# RS232.net
KiCad netlist of a schematic drawn in Altium Designer
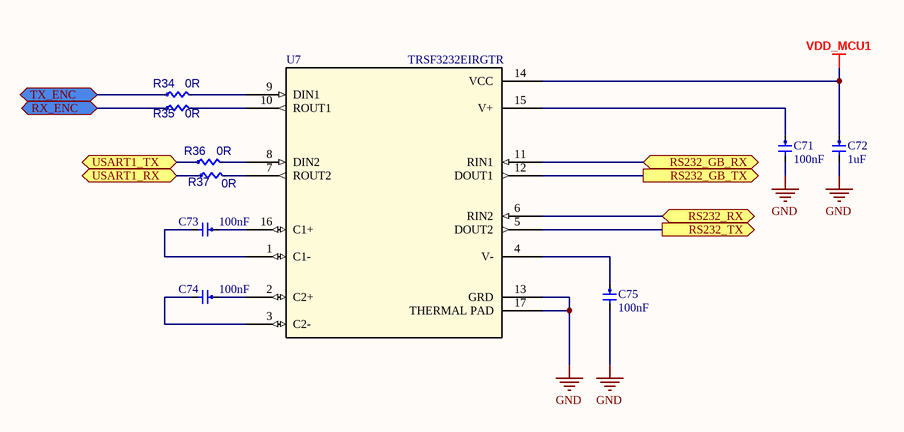
[diagram p0: RS232.SchDoc]

(export (version "E")
  (design (tool "Eeschema 10.0.6"))
  (components
    (comp (ref "C71")
      (value "GRM155R71H104KE14D")
      (footprint "CAP0402")
      (description "CAP CER 0.1UF 50V X7R 0402")
      (fields
        (field (name "TOLERANCE") "10%")
        (field (name "CAPACITANCE") "100nF")
        (field (name "VOLTAGE") "50V")
      )
      (libsource (lib "CH961_CARRIER") (part "CMP-01036-1"))
    )
    (comp (ref "C72")
      (value "CC0402KRX5R8BB105")
      (footprint "CAP0402")
      (description "CAP CER 1UF 25V X5R 0402")
      (fields
        (field (name "VOLTAGE") "25V")
        (field (name "TOLERANCE") "10%")
        (field (name "CAPACITANCE") "1uF")
      )
      (libsource (lib "CH961_CARRIER") (part "CMP-00520-1"))
    )
    (comp (ref "C73")
      (value "GRM155R71H104KE14D")
      (footprint "CAP0402")
      (description "CAP CER 0.1UF 50V X7R 0402")
      (fields
        (field (name "TOLERANCE") "10%")
        (field (name "CAPACITANCE") "100nF")
        (field (name "VOLTAGE") "50V")
      )
      (libsource (lib "CH961_CARRIER") (part "CMP-01036-1"))
    )
    (comp (ref "C74")
      (value "GRM155R71H104KE14D")
      (footprint "CAP0402")
      (description "CAP CER 0.1UF 50V X7R 0402")
      (fields
        (field (name "TOLERANCE") "10%")
        (field (name "CAPACITANCE") "100nF")
        (field (name "VOLTAGE") "50V")
      )
      (libsource (lib "CH961_CARRIER") (part "CMP-01036-1"))
    )
    (comp (ref "C75")
      (value "GRM155R71H104KE14D")
      (footprint "CAP0402")
      (description "CAP CER 0.1UF 50V X7R 0402")
      (fields
        (field (name "TOLERANCE") "10%")
        (field (name "CAPACITANCE") "100nF")
        (field (name "VOLTAGE") "50V")
      )
      (libsource (lib "CH961_CARRIER") (part "CMP-01036-1"))
    )
    (comp (ref "R34")
      (value "ERJ-2RKF4701X")
      (footprint "RES0402")
      (description "RES SMD 4.7K OHM 1% 1/10W 0402")
      (fields (field (name "TOLERANCE") "1%") (field (name "RESISTANCE") "0R"))
      (libsource (lib "rtr") (part "CMP-00607-1"))
    )
    (comp (ref "R35")
      (value "ERJ-2RKF4701X")
      (footprint "RES0402")
      (description "RES SMD 4.7K OHM 1% 1/10W 0402")
      (fields (field (name "TOLERANCE") "1%") (field (name "RESISTANCE") "0R"))
      (libsource (lib "rtr") (part "CMP-00607-1"))
    )
    (comp (ref "R36")
      (value "ERJ-2RKF4701X")
      (footprint "RES0402")
      (description "RES SMD 4.7K OHM 1% 1/10W 0402")
      (fields (field (name "TOLERANCE") "1%") (field (name "RESISTANCE") "0R"))
      (libsource (lib "rtr") (part "CMP-00607-1"))
    )
    (comp (ref "R37")
      (value "ERJ-2RKF4701X")
      (footprint "RES0402")
      (description "RES SMD 4.7K OHM 1% 1/10W 0402")
      (fields (field (name "TOLERANCE") "1%") (field (name "RESISTANCE") "0R"))
      (libsource (lib "rtr") (part "CMP-00607-1"))
    )
    (comp (ref "U7")
      (value "TRSF3232EIRGTR")
      (footprint "TRSF3232EIRGTR")
      (description "No Description Available")
      (libsource (lib "TRSF3232EIRGTR") (part "TRSF3232EIRGTR"))
    )
  )
  (nets
    (net (code "1") (name "/RS232_GB_RX") (class "Default")
      (node (ref "U7") (pin "11") (pinfunction "RIN1_11") (pintype "input"))
    )
    (net (code "2") (name "/RS232_GB_TX") (class "Default")
      (node (ref "U7") (pin "12") (pinfunction "DOUT1_12") (pintype "output"))
    )
    (net (code "3") (name "/RS232_RX") (class "Default")
      (node (ref "U7") (pin "6") (pinfunction "RIN2_6") (pintype "input"))
    )
    (net (code "4") (name "/RS232_TX") (class "Default")
      (node (ref "U7") (pin "5") (pinfunction "DOUT2_5") (pintype "output"))
    )
    (net (code "5") (name "/RX_ENC") (class "Default")
      (node (ref "R35") (pin "1") (pinfunction "1_1") (pintype "passive"))
    )
    (net (code "6") (name "/TX_ENC") (class "Default")
      (node (ref "R34") (pin "1") (pinfunction "1_1") (pintype "passive"))
    )
    (net (code "7") (name "/USART1_RX") (class "Default")
      (node (ref "R37") (pin "1") (pinfunction "1_1") (pintype "passive"))
    )
    (net (code "8") (name "/USART1_TX") (class "Default")
      (node (ref "R36") (pin "1") (pinfunction "1_1") (pintype "passive"))
    )
    (net (code "9") (name "GND") (class "Default")
      (node (ref "C71") (pin "2") (pinfunction "2_2") (pintype "passive"))
      (node (ref "C72") (pin "2") (pinfunction "2_2") (pintype "passive"))
      (node (ref "C75") (pin "2") (pinfunction "2_2") (pintype "passive"))
      (node (ref "U7") (pin "13") (pinfunction "GRD_13") (pintype "passive"))
      (node (ref "U7") (pin "17") (pinfunction "THERMAL_PAD_17") (pintype "passive"))
    )
    (net (code "10") (name "Net-(U7-C1+)") (class "Default")
      (node (ref "C73") (pin "1") (pinfunction "1_1") (pintype "passive"))
      (node (ref "U7") (pin "16") (pinfunction "C1+_16") (pintype "bidirectional"))
    )
    (net (code "11") (name "Net-(U7-C1-)") (class "Default")
      (node (ref "C73") (pin "2") (pinfunction "2_2") (pintype "passive"))
      (node (ref "U7") (pin "1") (pinfunction "C1-_1") (pintype "bidirectional"))
    )
    (net (code "12") (name "Net-(U7-C2+)") (class "Default")
      (node (ref "C74") (pin "1") (pinfunction "1_1") (pintype "passive"))
      (node (ref "U7") (pin "2") (pinfunction "C2+_2") (pintype "bidirectional"))
    )
    (net (code "13") (name "Net-(U7-C2-)") (class "Default")
      (node (ref "C74") (pin "2") (pinfunction "2_2") (pintype "passive"))
      (node (ref "U7") (pin "3") (pinfunction "C2-_3") (pintype "bidirectional"))
    )
    (net (code "14") (name "Net-(U7-DIN1)") (class "Default")
      (node (ref "R34") (pin "2") (pinfunction "2_2") (pintype "passive"))
      (node (ref "U7") (pin "9") (pinfunction "DIN1_9") (pintype "input"))
    )
    (net (code "15") (name "Net-(U7-DIN2)") (class "Default")
      (node (ref "R36") (pin "2") (pinfunction "2_2") (pintype "passive"))
      (node (ref "U7") (pin "8") (pinfunction "DIN2_8") (pintype "input"))
    )
    (net (code "16") (name "Net-(U7-ROUT1)") (class "Default")
      (node (ref "R35") (pin "2") (pinfunction "2_2") (pintype "passive"))
      (node (ref "U7") (pin "10") (pinfunction "ROUT1_10") (pintype "output"))
    )
    (net (code "17") (name "Net-(U7-ROUT2)") (class "Default")
      (node (ref "R37") (pin "2") (pinfunction "2_2") (pintype "passive"))
      (node (ref "U7") (pin "7") (pinfunction "ROUT2_7") (pintype "output"))
    )
    (net (code "18") (name "Net-(U7-V+)") (class "Default")
      (node (ref "C71") (pin "1") (pinfunction "1_1") (pintype "passive"))
      (node (ref "U7") (pin "15") (pinfunction "V+_15") (pintype "power_in"))
    )
    (net (code "19") (name "Net-(U7-V-)") (class "Default")
      (node (ref "C75") (pin "1") (pinfunction "1_1") (pintype "passive"))
      (node (ref "U7") (pin "4") (pinfunction "V-_4") (pintype "power_in"))
    )
    (net (code "20") (name "VDD_MCU1") (class "Default")
      (node (ref "C72") (pin "1") (pinfunction "1_1") (pintype "passive"))
      (node (ref "U7") (pin "14") (pinfunction "VCC_14") (pintype "power_in"))
    )
  )
)
